# 05_LMS7002M_Misc.net
KiCad netlist of a schematic drawn in Altium Designer
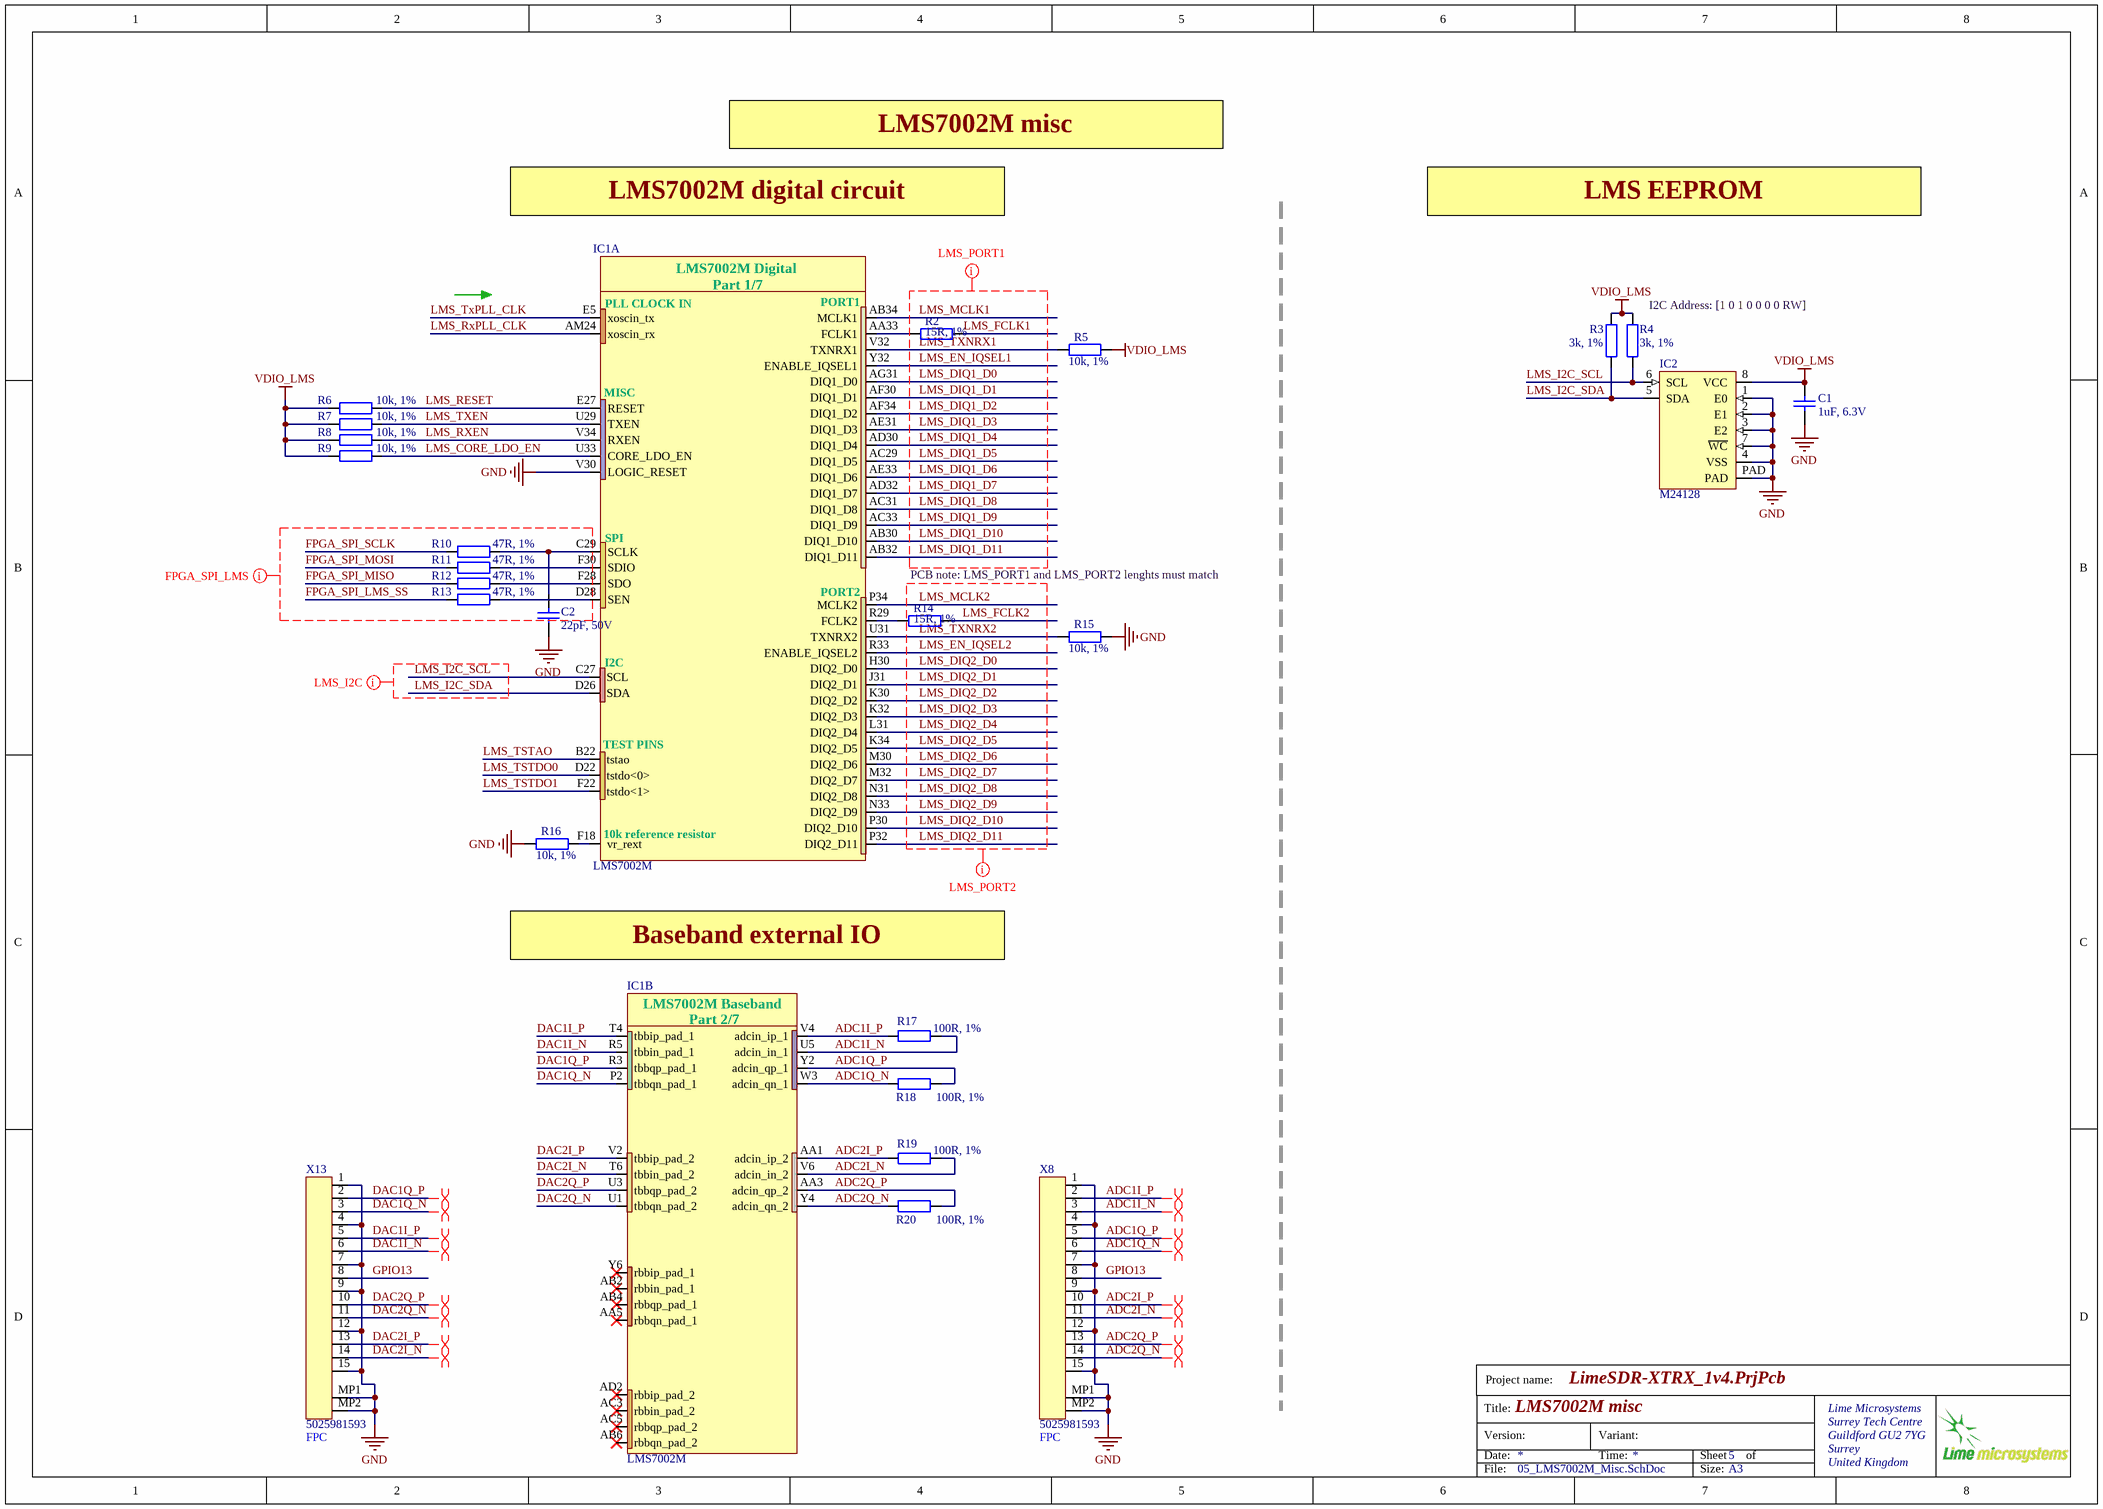
[diagram p0: 05_LMS7002M_Misc.SchDoc]

(export (version "E")
  (design (tool "Eeschema 10.0.6"))
  (components
    (comp (ref "C1")
      (value "1uF, 6.3V")
      (footprint "CAP0201")
      (fields (field (name "TOLERANCE") "±20%") (field (name "MANUFACTURER") "TDK Corporation"))
      (libsource (lib "LimeMicroAltiumLib_schLib") (part "Cap_0402"))
    )
    (comp (ref "C2")
      (value "22pF, 50V")
      (footprint "CAP0201")
      (fields
        (field (name "MANUFACTURER") "Murata")
        (field (name "TOLERANCE") "5%")
        (field (name "VOLTAGE") "50V")
      )
      (libsource (lib "LimeMicroAltiumLib_schLib") (part "Cap_0402"))
    )
    (comp (ref "IC1")
      (value "LMS7002M")
      (footprint "LMS7002M_v5_LESS_SILK")
      (description "Schematic symbol revision 4. Default footprint - 0.31mm pad")
      (fields (field (name "MANUFACTURER") "Lime Microsystems"))
      (libsource (lib "LimeMicroAltiumLib_schLib_r04") (part "LMS7002Mr4"))
    )
    (comp (ref "IC2")
      (value "M24128")
      (footprint "M24128-DFMC6TG")
      (fields (field (name "MANUFACTURER") "STMicroelectronics"))
      (libsource (lib "LimeMicroAltiumLib_schLib") (part "M24128-DFMC6TG"))
    )
    (comp (ref "R2")
      (value "15R, 1%")
      (footprint "RES0201")
      (fields (field (name "MANUFACTURER") "Yageo") (field (name "TOLERANCE") "1%"))
      (libsource (lib "LimeFPGAboard_schLib") (part "Res_0402"))
    )
    (comp (ref "R3")
      (value "3k, 1%")
      (footprint "RES0201")
      (fields (field (name "MANUFACTURER") "Yageo") (field (name "TOLERANCE") "1%"))
      (libsource (lib "LimeFPGAboard_schLib") (part "Res_0402"))
    )
    (comp (ref "R4")
      (value "3k, 1%")
      (footprint "RES0201")
      (fields (field (name "MANUFACTURER") "Yageo") (field (name "TOLERANCE") "1%"))
      (libsource (lib "LimeFPGAboard_schLib") (part "Res_0402"))
    )
    (comp (ref "R5")
      (value "10k, 1%")
      (footprint "RES0201")
      (fields (field (name "MANUFACTURER") "Yageo") (field (name "TOLERANCE") "1%"))
      (libsource (lib "LimeFPGAboard_schLib") (part "Res_0402"))
    )
    (comp (ref "R6")
      (value "10k, 1%")
      (footprint "RES0201")
      (fields (field (name "MANUFACTURER") "Yageo") (field (name "TOLERANCE") "1%"))
      (libsource (lib "LimeFPGAboard_schLib") (part "Res_0402"))
    )
    (comp (ref "R7")
      (value "10k, 1%")
      (footprint "RES0201")
      (fields (field (name "MANUFACTURER") "Yageo") (field (name "TOLERANCE") "1%"))
      (libsource (lib "LimeFPGAboard_schLib") (part "Res_0402"))
    )
    (comp (ref "R8")
      (value "10k, 1%")
      (footprint "RES0201")
      (fields (field (name "MANUFACTURER") "Yageo") (field (name "TOLERANCE") "1%"))
      (libsource (lib "LimeFPGAboard_schLib") (part "Res_0402"))
    )
    (comp (ref "R9")
      (value "10k, 1%")
      (footprint "RES0201")
      (fields (field (name "MANUFACTURER") "Yageo") (field (name "TOLERANCE") "1%"))
      (libsource (lib "LimeFPGAboard_schLib") (part "Res_0402"))
    )
    (comp (ref "R10")
      (value "47R, 1%")
      (footprint "RES0201")
      (fields (field (name "MANUFACTURER") "Yageo") (field (name "TOLERANCE") "1%"))
      (libsource (lib "LimeFPGAboard_schLib") (part "Res_0402"))
    )
    (comp (ref "R11")
      (value "47R, 1%")
      (footprint "RES0201")
      (fields (field (name "MANUFACTURER") "Yageo") (field (name "TOLERANCE") "1%"))
      (libsource (lib "LimeFPGAboard_schLib") (part "Res_0402"))
    )
    (comp (ref "R12")
      (value "47R, 1%")
      (footprint "RES0201")
      (fields (field (name "MANUFACTURER") "Yageo") (field (name "TOLERANCE") "1%"))
      (libsource (lib "LimeFPGAboard_schLib") (part "Res_0402"))
    )
    (comp (ref "R13")
      (value "47R, 1%")
      (footprint "RES0201")
      (fields (field (name "MANUFACTURER") "Yageo") (field (name "TOLERANCE") "1%"))
      (libsource (lib "LimeFPGAboard_schLib") (part "Res_0402"))
    )
    (comp (ref "R14")
      (value "15R, 1%")
      (footprint "RES0201")
      (fields (field (name "MANUFACTURER") "Yageo") (field (name "TOLERANCE") "1%"))
      (libsource (lib "LimeFPGAboard_schLib") (part "Res_0402"))
    )
    (comp (ref "R15")
      (value "10k, 1%")
      (footprint "RES0201")
      (fields (field (name "MANUFACTURER") "Yageo") (field (name "TOLERANCE") "1%"))
      (libsource (lib "LimeFPGAboard_schLib") (part "Res_0402"))
    )
    (comp (ref "R16")
      (value "10k, 1%")
      (footprint "RES0201")
      (fields (field (name "MANUFACTURER") "Yageo") (field (name "TOLERANCE") "1%"))
      (libsource (lib "LimeFPGAboard_schLib") (part "Res_0402"))
    )
    (comp (ref "R17")
      (value "100R, 1%")
      (footprint "RES0201")
      (fields (field (name "MANUFACTURER") "Yageo") (field (name "TOLERANCE") "1%"))
      (libsource (lib "LimeFPGAboard_schLib") (part "Res_0402"))
    )
    (comp (ref "R18")
      (value "100R, 1%")
      (footprint "RES0201")
      (fields (field (name "MANUFACTURER") "Yageo") (field (name "TOLERANCE") "1%"))
      (libsource (lib "LimeFPGAboard_schLib") (part "Res_0402"))
    )
    (comp (ref "R19")
      (value "100R, 1%")
      (footprint "RES0201")
      (fields (field (name "MANUFACTURER") "Yageo") (field (name "TOLERANCE") "1%"))
      (libsource (lib "LimeFPGAboard_schLib") (part "Res_0402"))
    )
    (comp (ref "R20")
      (value "100R, 1%")
      (footprint "RES0201")
      (fields (field (name "MANUFACTURER") "Yageo") (field (name "TOLERANCE") "1%"))
      (libsource (lib "LimeFPGAboard_schLib") (part "Res_0402"))
    )
    (comp (ref "X8")
      (value "5025981593")
      (footprint "5025981593_FPC_connector")
      (fields (field (name "MANUFACTURER") "Molex"))
      (libsource (lib "LimeMicroAltiumLib_schLib_r04") (part "5025981593_FPC_connector"))
    )
    (comp (ref "X13")
      (value "5025981593")
      (footprint "5025981593_FPC_connector")
      (fields (field (name "MANUFACTURER") "Molex"))
      (libsource (lib "LimeMicroAltiumLib_schLib_r04") (part "5025981593_FPC_connector"))
    )
  )
  (nets
    (net (code "1") (name "/ADC1I_N") (class "Default")
      (node (ref "IC1") (pin "U5") (pinfunction "adcin_in_1_U5") (pintype "passive"))
      (node (ref "R17") (pin "2") (pinfunction "2_2") (pintype "passive"))
      (node (ref "X8") (pin "3") (pinfunction "3_3") (pintype "passive"))
    )
    (net (code "2") (name "/ADC1I_P") (class "Default")
      (node (ref "IC1") (pin "V4") (pinfunction "adcin_ip_1_V4") (pintype "passive"))
      (node (ref "R17") (pin "1") (pinfunction "1_1") (pintype "passive"))
      (node (ref "X8") (pin "2") (pinfunction "2_2") (pintype "passive"))
    )
    (net (code "3") (name "/ADC1Q_N") (class "Default")
      (node (ref "IC1") (pin "W3") (pinfunction "adcin_qn_1_W3") (pintype "passive"))
      (node (ref "R18") (pin "1") (pinfunction "1_1") (pintype "passive"))
      (node (ref "X8") (pin "6") (pinfunction "6_6") (pintype "passive"))
    )
    (net (code "4") (name "/ADC1Q_P") (class "Default")
      (node (ref "IC1") (pin "Y2") (pinfunction "adcin_qp_1_Y2") (pintype "passive"))
      (node (ref "R18") (pin "2") (pinfunction "2_2") (pintype "passive"))
      (node (ref "X8") (pin "5") (pinfunction "5_5") (pintype "passive"))
    )
    (net (code "5") (name "/ADC2I_N") (class "Default")
      (node (ref "IC1") (pin "V6") (pinfunction "adcin_in_2_V6") (pintype "passive"))
      (node (ref "R19") (pin "2") (pinfunction "2_2") (pintype "passive"))
      (node (ref "X8") (pin "11") (pinfunction "11_11") (pintype "passive"))
    )
    (net (code "6") (name "/ADC2I_P") (class "Default")
      (node (ref "IC1") (pin "AA1") (pinfunction "adcin_ip_2_AA1") (pintype "passive"))
      (node (ref "R19") (pin "1") (pinfunction "1_1") (pintype "passive"))
      (node (ref "X8") (pin "10") (pinfunction "10_10") (pintype "passive"))
    )
    (net (code "7") (name "/ADC2Q_N") (class "Default")
      (node (ref "IC1") (pin "Y4") (pinfunction "adcin_qn_2_Y4") (pintype "passive"))
      (node (ref "R20") (pin "1") (pinfunction "1_1") (pintype "passive"))
      (node (ref "X8") (pin "14") (pinfunction "14_14") (pintype "passive"))
    )
    (net (code "8") (name "/ADC2Q_P") (class "Default")
      (node (ref "IC1") (pin "AA3") (pinfunction "adcin_qp_2_AA3") (pintype "passive"))
      (node (ref "R20") (pin "2") (pinfunction "2_2") (pintype "passive"))
      (node (ref "X8") (pin "13") (pinfunction "13_13") (pintype "passive"))
    )
    (net (code "9") (name "/DAC1I_N") (class "Default")
      (node (ref "IC1") (pin "R5") (pinfunction "tbbin_pad_1_R5") (pintype "passive"))
      (node (ref "X13") (pin "6") (pinfunction "6_6") (pintype "passive"))
    )
    (net (code "10") (name "/DAC1I_P") (class "Default")
      (node (ref "IC1") (pin "T4") (pinfunction "tbbip_pad_1_T4") (pintype "passive"))
      (node (ref "X13") (pin "5") (pinfunction "5_5") (pintype "passive"))
    )
    (net (code "11") (name "/DAC1Q_N") (class "Default")
      (node (ref "IC1") (pin "P2") (pinfunction "tbbqn_pad_1_P2") (pintype "passive"))
      (node (ref "X13") (pin "3") (pinfunction "3_3") (pintype "passive"))
    )
    (net (code "12") (name "/DAC1Q_P") (class "Default")
      (node (ref "IC1") (pin "R3") (pinfunction "tbbqp_pad_1_R3") (pintype "passive"))
      (node (ref "X13") (pin "2") (pinfunction "2_2") (pintype "passive"))
    )
    (net (code "13") (name "/DAC2I_N") (class "Default")
      (node (ref "IC1") (pin "T6") (pinfunction "tbbin_pad_2_T6") (pintype "passive"))
      (node (ref "X13") (pin "14") (pinfunction "14_14") (pintype "passive"))
    )
    (net (code "14") (name "/DAC2I_P") (class "Default")
      (node (ref "IC1") (pin "V2") (pinfunction "tbbip_pad_2_V2") (pintype "passive"))
      (node (ref "X13") (pin "13") (pinfunction "13_13") (pintype "passive"))
    )
    (net (code "15") (name "/DAC2Q_N") (class "Default")
      (node (ref "IC1") (pin "U1") (pinfunction "tbbqn_pad_2_U1") (pintype "passive"))
      (node (ref "X13") (pin "11") (pinfunction "11_11") (pintype "passive"))
    )
    (net (code "16") (name "/DAC2Q_P") (class "Default")
      (node (ref "IC1") (pin "U3") (pinfunction "tbbqp_pad_2_U3") (pintype "passive"))
      (node (ref "X13") (pin "10") (pinfunction "10_10") (pintype "passive"))
    )
    (net (code "17") (name "/FPGA_SPI_LMS_SS") (class "Default")
      (node (ref "R13") (pin "2") (pinfunction "2_2") (pintype "passive"))
    )
    (net (code "18") (name "/FPGA_SPI_MISO") (class "Default")
      (node (ref "R12") (pin "2") (pinfunction "2_2") (pintype "passive"))
    )
    (net (code "19") (name "/FPGA_SPI_MOSI") (class "Default")
      (node (ref "R11") (pin "2") (pinfunction "2_2") (pintype "passive"))
    )
    (net (code "20") (name "/FPGA_SPI_SCLK") (class "Default")
      (node (ref "R10") (pin "2") (pinfunction "2_2") (pintype "passive"))
    )
    (net (code "21") (name "/GPIO13") (class "Default")
      (node (ref "X13") (pin "8") (pinfunction "8_8") (pintype "passive"))
      (node (ref "X8") (pin "8") (pinfunction "8_8") (pintype "passive"))
    )
    (net (code "22") (name "/LMS_CORE_LDO_EN") (class "Default")
      (node (ref "IC1") (pin "U33") (pinfunction "CORE_LDO_EN_U33") (pintype "passive"))
      (node (ref "R9") (pin "1") (pinfunction "1_1") (pintype "passive"))
    )
    (net (code "23") (name "/LMS_DIQ1_D0") (class "Default")
      (node (ref "IC1") (pin "AG31") (pinfunction "DIQ1_D0_AG31") (pintype "passive"))
    )
    (net (code "24") (name "/LMS_DIQ1_D1") (class "Default")
      (node (ref "IC1") (pin "AF30") (pinfunction "DIQ1_D1_AF30") (pintype "passive"))
    )
    (net (code "25") (name "/LMS_DIQ1_D2") (class "Default")
      (node (ref "IC1") (pin "AF34") (pinfunction "DIQ1_D2_AF34") (pintype "passive"))
    )
    (net (code "26") (name "/LMS_DIQ1_D3") (class "Default")
      (node (ref "IC1") (pin "AE31") (pinfunction "DIQ1_D3_AE31") (pintype "passive"))
    )
    (net (code "27") (name "/LMS_DIQ1_D4") (class "Default")
      (node (ref "IC1") (pin "AD30") (pinfunction "DIQ1_D4_AD30") (pintype "passive"))
    )
    (net (code "28") (name "/LMS_DIQ1_D5") (class "Default")
      (node (ref "IC1") (pin "AC29") (pinfunction "DIQ1_D5_AC29") (pintype "passive"))
    )
    (net (code "29") (name "/LMS_DIQ1_D6") (class "Default")
      (node (ref "IC1") (pin "AE33") (pinfunction "DIQ1_D6_AE33") (pintype "passive"))
    )
    (net (code "30") (name "/LMS_DIQ1_D7") (class "Default")
      (node (ref "IC1") (pin "AD32") (pinfunction "DIQ1_D7_AD32") (pintype "passive"))
    )
    (net (code "31") (name "/LMS_DIQ1_D8") (class "Default")
      (node (ref "IC1") (pin "AC31") (pinfunction "DIQ1_D8_AC31") (pintype "passive"))
    )
    (net (code "32") (name "/LMS_DIQ1_D9") (class "Default")
      (node (ref "IC1") (pin "AC33") (pinfunction "DIQ1_D9_AC33") (pintype "passive"))
    )
    (net (code "33") (name "/LMS_DIQ1_D10") (class "Default")
      (node (ref "IC1") (pin "AB30") (pinfunction "DIQ1_D10_AB30") (pintype "passive"))
    )
    (net (code "34") (name "/LMS_DIQ1_D11") (class "Default")
      (node (ref "IC1") (pin "AB32") (pinfunction "DIQ1_D11_AB32") (pintype "passive"))
    )
    (net (code "35") (name "/LMS_DIQ2_D0") (class "Default")
      (node (ref "IC1") (pin "H30") (pinfunction "DIQ2_D0_H30") (pintype "passive"))
    )
    (net (code "36") (name "/LMS_DIQ2_D1") (class "Default")
      (node (ref "IC1") (pin "J31") (pinfunction "DIQ2_D1_J31") (pintype "passive"))
    )
    (net (code "37") (name "/LMS_DIQ2_D2") (class "Default")
      (node (ref "IC1") (pin "K30") (pinfunction "DIQ2_D2_K30") (pintype "passive"))
    )
    (net (code "38") (name "/LMS_DIQ2_D3") (class "Default")
      (node (ref "IC1") (pin "K32") (pinfunction "DIQ2_D3_K32") (pintype "passive"))
    )
    (net (code "39") (name "/LMS_DIQ2_D4") (class "Default")
      (node (ref "IC1") (pin "L31") (pinfunction "DIQ2_D4_L31") (pintype "passive"))
    )
    (net (code "40") (name "/LMS_DIQ2_D5") (class "Default")
      (node (ref "IC1") (pin "K34") (pinfunction "DIQ2_D5_K34") (pintype "passive"))
    )
    (net (code "41") (name "/LMS_DIQ2_D6") (class "Default")
      (node (ref "IC1") (pin "M30") (pinfunction "DIQ2_D6_M30") (pintype "passive"))
    )
    (net (code "42") (name "/LMS_DIQ2_D7") (class "Default")
      (node (ref "IC1") (pin "M32") (pinfunction "DIQ2_D7_M32") (pintype "passive"))
    )
    (net (code "43") (name "/LMS_DIQ2_D8") (class "Default")
      (node (ref "IC1") (pin "N31") (pinfunction "DIQ2_D8_N31") (pintype "passive"))
    )
    (net (code "44") (name "/LMS_DIQ2_D9") (class "Default")
      (node (ref "IC1") (pin "N33") (pinfunction "DIQ2_D9_N33") (pintype "passive"))
    )
    (net (code "45") (name "/LMS_DIQ2_D10") (class "Default")
      (node (ref "IC1") (pin "P30") (pinfunction "DIQ2_D10_P30") (pintype "passive"))
    )
    (net (code "46") (name "/LMS_DIQ2_D11") (class "Default")
      (node (ref "IC1") (pin "P32") (pinfunction "DIQ2_D11_P32") (pintype "passive"))
    )
    (net (code "47") (name "/LMS_EN_IQSEL1") (class "Default")
      (node (ref "IC1") (pin "Y32") (pinfunction "ENABLE_IQSEL1_Y32") (pintype "passive"))
    )
    (net (code "48") (name "/LMS_EN_IQSEL2") (class "Default")
      (node (ref "IC1") (pin "R33") (pinfunction "ENABLE_IQSEL2_R33") (pintype "passive"))
    )
    (net (code "49") (name "/LMS_FCLK1") (class "Default")
      (node (ref "R2") (pin "1") (pinfunction "1_1") (pintype "passive"))
    )
    (net (code "50") (name "/LMS_FCLK2") (class "Default")
      (node (ref "R14") (pin "1") (pinfunction "1_1") (pintype "passive"))
    )
    (net (code "51") (name "/LMS_I2C_SCL") (class "Default")
      (node (ref "IC1") (pin "C27") (pinfunction "SCL_C27") (pintype "passive"))
      (node (ref "IC2") (pin "6") (pinfunction "SCL_6") (pintype "input"))
      (node (ref "R4") (pin "1") (pinfunction "1_1") (pintype "passive"))
    )
    (net (code "52") (name "/LMS_I2C_SDA") (class "Default")
      (node (ref "IC1") (pin "D26") (pinfunction "SDA_D26") (pintype "passive"))
      (node (ref "IC2") (pin "5") (pinfunction "SDA_5") (pintype "bidirectional"))
      (node (ref "R3") (pin "1") (pinfunction "1_1") (pintype "passive"))
    )
    (net (code "53") (name "/LMS_MCLK1") (class "Default")
      (node (ref "IC1") (pin "AB34") (pinfunction "MCLK1_AB34") (pintype "passive"))
    )
    (net (code "54") (name "/LMS_MCLK2") (class "Default")
      (node (ref "IC1") (pin "P34") (pinfunction "MCLK2_P34") (pintype "passive"))
    )
    (net (code "55") (name "/LMS_RESET") (class "Default")
      (node (ref "IC1") (pin "E27") (pinfunction "RESET_E27") (pintype "passive"))
      (node (ref "R6") (pin "1") (pinfunction "1_1") (pintype "passive"))
    )
    (net (code "56") (name "/LMS_RXEN") (class "Default")
      (node (ref "IC1") (pin "V34") (pinfunction "RXEN_V34") (pintype "passive"))
      (node (ref "R8") (pin "1") (pinfunction "1_1") (pintype "passive"))
    )
    (net (code "57") (name "/LMS_RxPLL_CLK") (class "Default")
      (node (ref "IC1") (pin "AM24") (pinfunction "xoscin_rx_AM24") (pintype "passive"))
    )
    (net (code "58") (name "/LMS_TSTAO") (class "Default")
      (node (ref "IC1") (pin "B22") (pinfunction "tstao_B22") (pintype "passive"))
    )
    (net (code "59") (name "/LMS_TSTDO0") (class "Default")
      (node (ref "IC1") (pin "D22") (pinfunction "tstdo<0>_D22") (pintype "passive"))
    )
    (net (code "60") (name "/LMS_TSTDO1") (class "Default")
      (node (ref "IC1") (pin "F22") (pinfunction "tstdo<1>_F22") (pintype "passive"))
    )
    (net (code "61") (name "/LMS_TXEN") (class "Default")
      (node (ref "IC1") (pin "U29") (pinfunction "TXEN_U29") (pintype "passive"))
      (node (ref "R7") (pin "1") (pinfunction "1_1") (pintype "passive"))
    )
    (net (code "62") (name "/LMS_TXNRX1") (class "Default")
      (node (ref "IC1") (pin "V32") (pinfunction "TXNRX1_V32") (pintype "passive"))
      (node (ref "R5") (pin "2") (pinfunction "2_2") (pintype "passive"))
    )
    (net (code "63") (name "/LMS_TXNRX2") (class "Default")
      (node (ref "IC1") (pin "U31") (pinfunction "TXNRX2_U31") (pintype "passive"))
      (node (ref "R15") (pin "2") (pinfunction "2_2") (pintype "passive"))
    )
    (net (code "64") (name "/LMS_TxPLL_CLK") (class "Default")
      (node (ref "IC1") (pin "E5") (pinfunction "xoscin_tx_E5") (pintype "passive"))
    )
    (net (code "65") (name "GND") (class "Default")
      (node (ref "C1") (pin "2") (pinfunction "2_2") (pintype "passive"))
      (node (ref "C2") (pin "1") (pinfunction "1_1") (pintype "passive"))
      (node (ref "IC1") (pin "V30") (pinfunction "LOGIC_RESET_V30") (pintype "passive"))
      (node (ref "IC2") (pin "1") (pinfunction "E0_1") (pintype "input"))
      (node (ref "IC2") (pin "2") (pinfunction "E1_2") (pintype "input"))
      (node (ref "IC2") (pin "3") (pinfunction "E2_3") (pintype "input"))
      (node (ref "IC2") (pin "4") (pinfunction "VSS_4") (pintype "power_in"))
      (node (ref "IC2") (pin "7") (pinfunction "~{WC}_7") (pintype "input"))
      (node (ref "IC2") (pin "PAD") (pinfunction "PAD_PAD") (pintype "power_in"))
      (node (ref "R15") (pin "1") (pinfunction "1_1") (pintype "passive"))
      (node (ref "R16") (pin "2") (pinfunction "2_2") (pintype "passive"))
      (node (ref "X13") (pin "1") (pinfunction "1_1") (pintype "passive"))
      (node (ref "X13") (pin "12") (pinfunction "12_12") (pintype "passive"))
      (node (ref "X13") (pin "15") (pinfunction "15_15") (pintype "passive"))
      (node (ref "X13") (pin "4") (pinfunction "4_4") (pintype "passive"))
      (node (ref "X13") (pin "7") (pinfunction "7_7") (pintype "passive"))
      (node (ref "X13") (pin "9") (pinfunction "9_9") (pintype "passive"))
      (node (ref "X13") (pin "MP1") (pinfunction "MP1_MP1") (pintype "passive"))
      (node (ref "X13") (pin "MP2") (pinfunction "MP2_MP2") (pintype "passive"))
      (node (ref "X8") (pin "1") (pinfunction "1_1") (pintype "passive"))
      (node (ref "X8") (pin "12") (pinfunction "12_12") (pintype "passive"))
      (node (ref "X8") (pin "15") (pinfunction "15_15") (pintype "passive"))
      (node (ref "X8") (pin "4") (pinfunction "4_4") (pintype "passive"))
      (node (ref "X8") (pin "7") (pinfunction "7_7") (pintype "passive"))
      (node (ref "X8") (pin "9") (pinfunction "9_9") (pintype "passive"))
      (node (ref "X8") (pin "MP1") (pinfunction "MP1_MP1") (pintype "passive"))
      (node (ref "X8") (pin "MP2") (pinfunction "MP2_MP2") (pintype "passive"))
    )
    (net (code "66") (name "Net-(IC1A-FCLK1)") (class "Default")
      (node (ref "IC1") (pin "AA33") (pinfunction "FCLK1_AA33") (pintype "passive"))
      (node (ref "R2") (pin "2") (pinfunction "2_2") (pintype "passive"))
    )
    (net (code "67") (name "Net-(IC1A-FCLK2)") (class "Default")
      (node (ref "IC1") (pin "R29") (pinfunction "FCLK2_R29") (pintype "passive"))
      (node (ref "R14") (pin "2") (pinfunction "2_2") (pintype "passive"))
    )
    (net (code "68") (name "Net-(IC1A-SCLK)") (class "Default")
      (node (ref "C2") (pin "2") (pinfunction "2_2") (pintype "passive"))
      (node (ref "IC1") (pin "C29") (pinfunction "SCLK_C29") (pintype "passive"))
      (node (ref "R10") (pin "1") (pinfunction "1_1") (pintype "passive"))
    )
    (net (code "69") (name "Net-(IC1A-SDIO)") (class "Default")
      (node (ref "IC1") (pin "F30") (pinfunction "SDIO_F30") (pintype "passive"))
      (node (ref "R11") (pin "1") (pinfunction "1_1") (pintype "passive"))
    )
    (net (code "70") (name "Net-(IC1A-SDO)") (class "Default")
      (node (ref "IC1") (pin "F28") (pinfunction "SDO_F28") (pintype "passive"))
      (node (ref "R12") (pin "1") (pinfunction "1_1") (pintype "passive"))
    )
    (net (code "71") (name "Net-(IC1A-SEN)") (class "Default")
      (node (ref "IC1") (pin "D28") (pinfunction "SEN_D28") (pintype "passive"))
      (node (ref "R13") (pin "1") (pinfunction "1_1") (pintype "passive"))
    )
    (net (code "72") (name "Net-(IC1A-vr_rext)") (class "Default")
      (node (ref "IC1") (pin "F18") (pinfunction "vr_rext_F18") (pintype "passive"))
      (node (ref "R16") (pin "1") (pinfunction "1_1") (pintype "passive"))
    )
    (net (code "73") (name "VDIO_LMS") (class "Default")
      (node (ref "C1") (pin "1") (pinfunction "1_1") (pintype "passive"))
      (node (ref "IC2") (pin "8") (pinfunction "VCC_8") (pintype "power_in"))
      (node (ref "R3") (pin "2") (pinfunction "2_2") (pintype "passive"))
      (node (ref "R4") (pin "2") (pinfunction "2_2") (pintype "passive"))
      (node (ref "R5") (pin "1") (pinfunction "1_1") (pintype "passive"))
      (node (ref "R6") (pin "2") (pinfunction "2_2") (pintype "passive"))
      (node (ref "R7") (pin "2") (pinfunction "2_2") (pintype "passive"))
      (node (ref "R8") (pin "2") (pinfunction "2_2") (pintype "passive"))
      (node (ref "R9") (pin "2") (pinfunction "2_2") (pintype "passive"))
    )
    (net (code "74") (name "unconnected-(IC1B-rbbin_pad_1-PadAB2)") (class "Default")
      (node (ref "IC1") (pin "AB2") (pinfunction "rbbin_pad_1_AB2") (pintype "passive+no_connect"))
    )
    (net (code "75") (name "unconnected-(IC1B-rbbin_pad_2-PadAC3)") (class "Default")
      (node (ref "IC1") (pin "AC3") (pinfunction "rbbin_pad_2_AC3") (pintype "passive+no_connect"))
    )
    (net (code "76") (name "unconnected-(IC1B-rbbip_pad_1-PadY6)") (class "Default")
      (node (ref "IC1") (pin "Y6") (pinfunction "rbbip_pad_1_Y6") (pintype "passive+no_connect"))
    )
    (net (code "77") (name "unconnected-(IC1B-rbbip_pad_2-PadAD2)") (class "Default")
      (node (ref "IC1") (pin "AD2") (pinfunction "rbbip_pad_2_AD2") (pintype "passive+no_connect"))
    )
    (net (code "78") (name "unconnected-(IC1B-rbbqn_pad_1-PadAA5)") (class "Default")
      (node (ref "IC1") (pin "AA5") (pinfunction "rbbqn_pad_1_AA5") (pintype "passive+no_connect"))
    )
    (net (code "79") (name "unconnected-(IC1B-rbbqn_pad_2-PadAB6)") (class "Default")
      (node (ref "IC1") (pin "AB6") (pinfunction "rbbqn_pad_2_AB6") (pintype "passive+no_connect"))
    )
    (net (code "80") (name "unconnected-(IC1B-rbbqp_pad_1-PadAB4)") (class "Default")
      (node (ref "IC1") (pin "AB4") (pinfunction "rbbqp_pad_1_AB4") (pintype "passive+no_connect"))
    )
    (net (code "81") (name "unconnected-(IC1B-rbbqp_pad_2-PadAC5)") (class "Default")
      (node (ref "IC1") (pin "AC5") (pinfunction "rbbqp_pad_2_AC5") (pintype "passive+no_connect"))
    )
  )
)
